# gimbal_controller.net
KiCad netlist of a schematic drawn in EAGLE
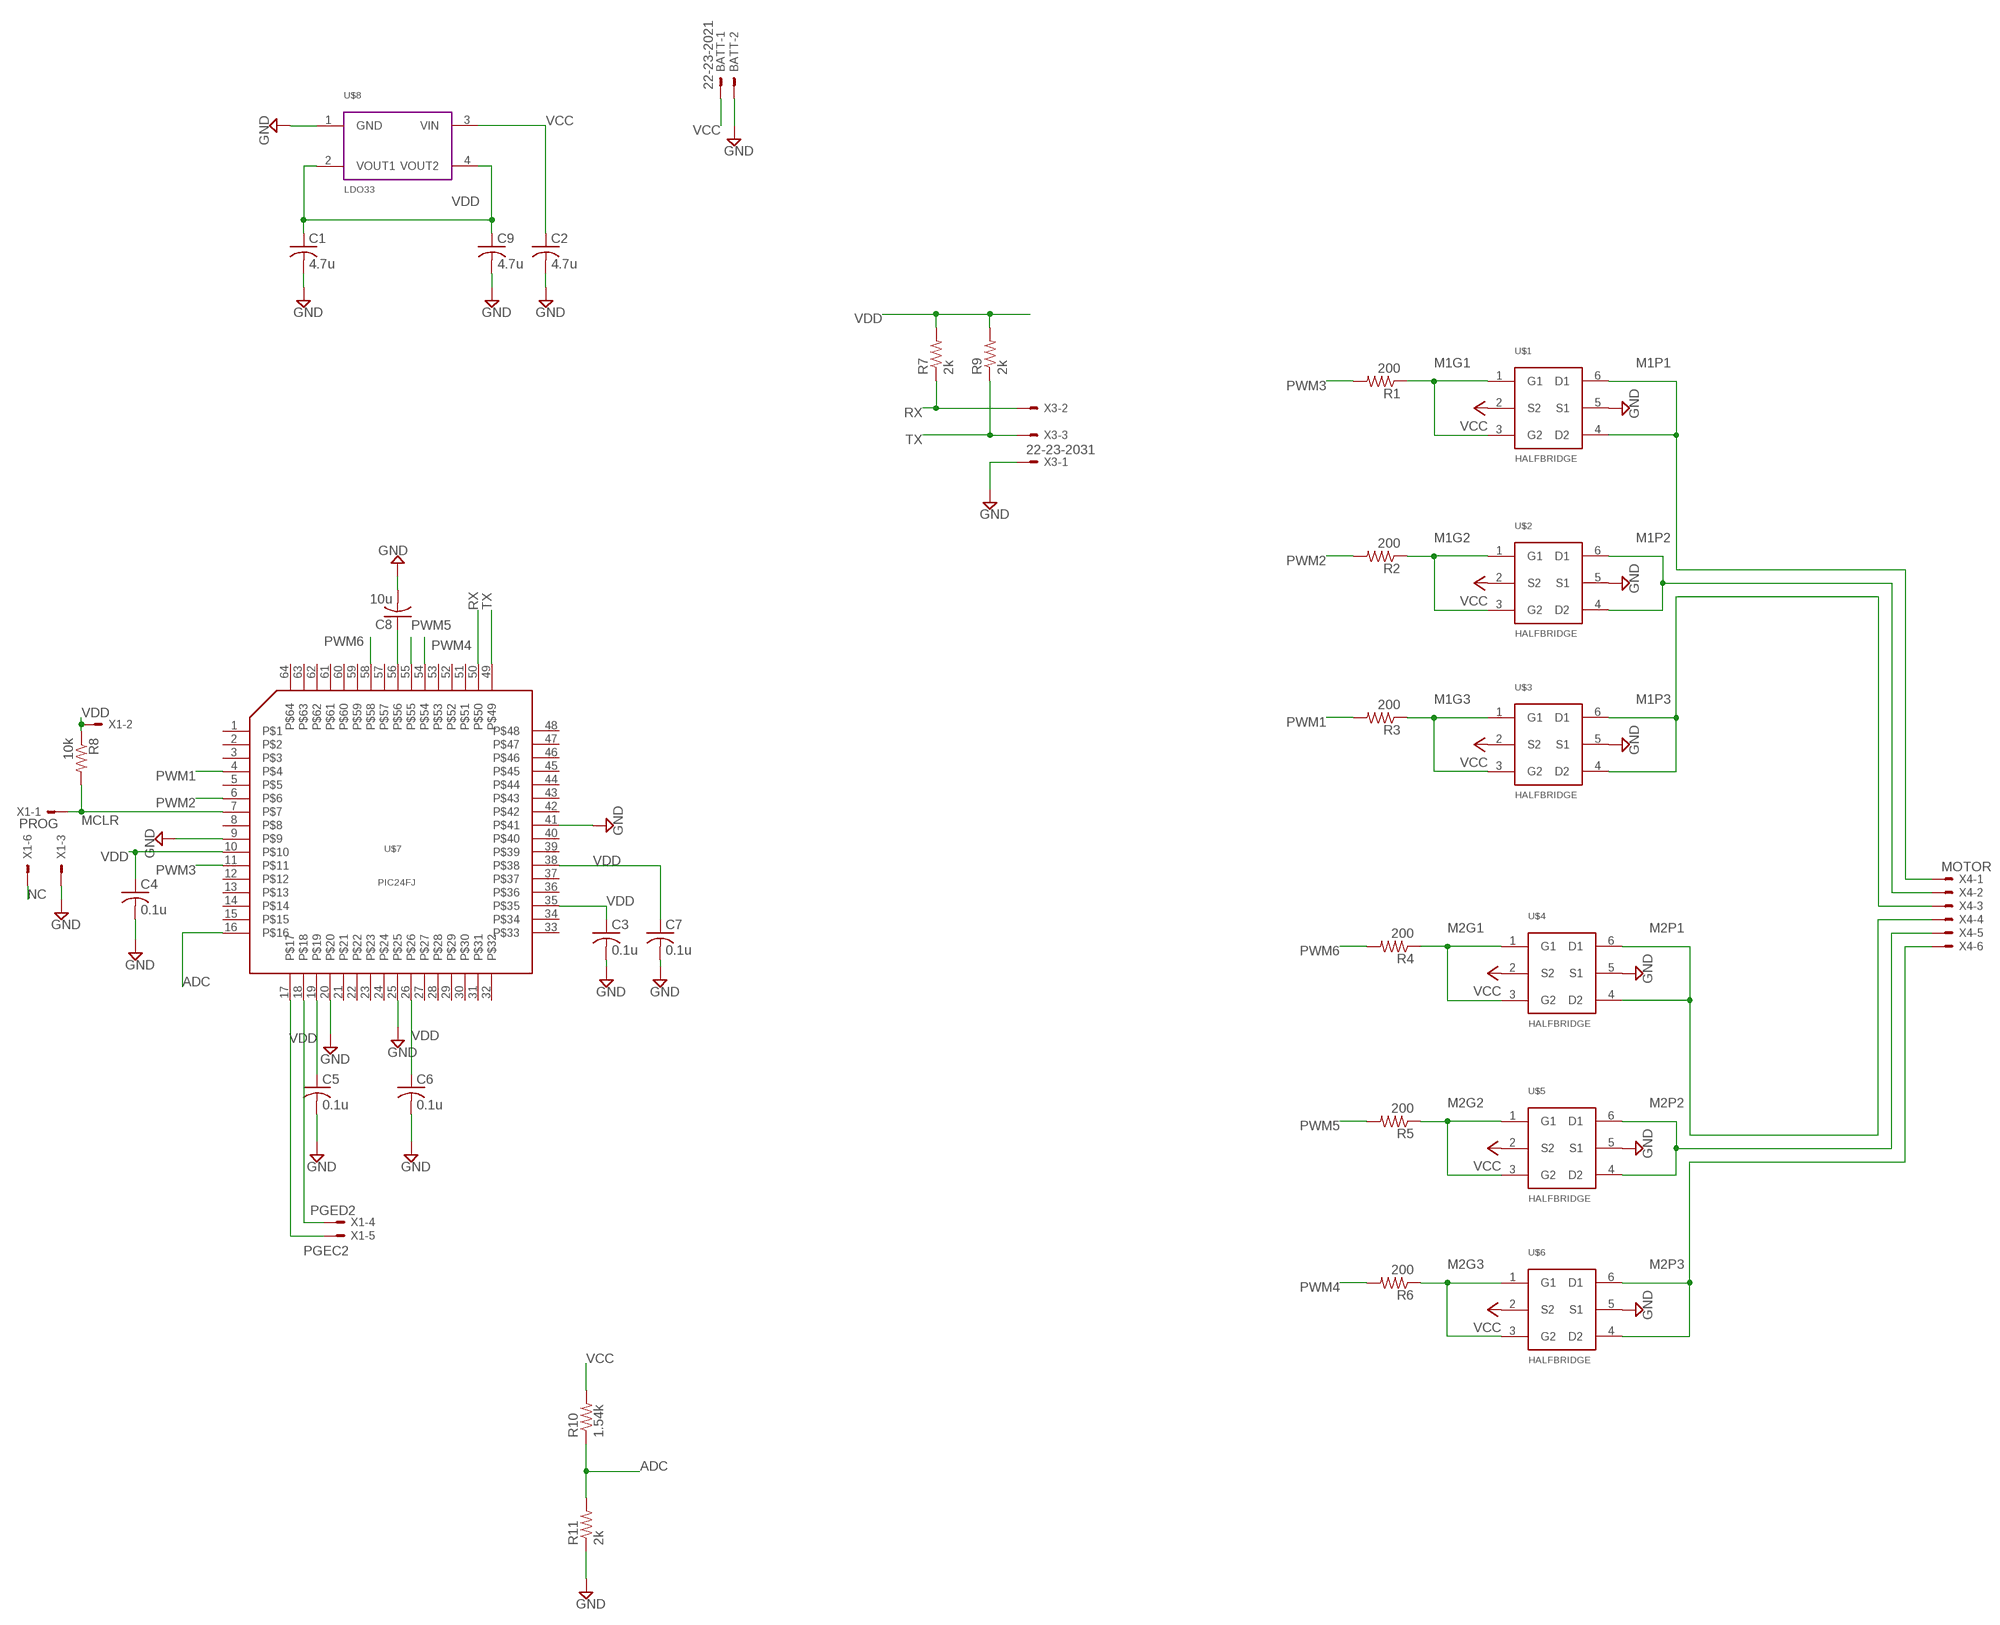
[diagram p0: schematic, sheet 1]

(export (version "E")
  (design (tool "Eeschema 10.0.6"))
  (components
    (comp (ref "BATT")
      (value "22-23-2021")
      (footprint "eagle-import:22-23-2021")
      (fields (field (name "MF") "MOLEX"))
      (libsource (lib "eagle-import") (part "22-23-2021"))
    )
    (comp (ref "C1")
      (value "4.7u")
      (footprint "eagle-import:C0805")
      (libsource (lib "eagle-import") (part "C-USC0805"))
    )
    (comp (ref "C2")
      (value "4.7u")
      (footprint "eagle-import:C0805")
      (libsource (lib "eagle-import") (part "C-USC0805"))
    )
    (comp (ref "C3")
      (value "0.1u")
      (footprint "eagle-import:C0805")
      (libsource (lib "eagle-import") (part "C-USC0805"))
    )
    (comp (ref "C4")
      (value "0.1u")
      (footprint "eagle-import:C0805")
      (libsource (lib "eagle-import") (part "C-USC0805"))
    )
    (comp (ref "C5")
      (value "0.1u")
      (footprint "eagle-import:C0805")
      (libsource (lib "eagle-import") (part "C-USC0805"))
    )
    (comp (ref "C6")
      (value "0.1u")
      (footprint "eagle-import:C0805")
      (libsource (lib "eagle-import") (part "C-USC0805"))
    )
    (comp (ref "C7")
      (value "0.1u")
      (footprint "eagle-import:C0805")
      (libsource (lib "eagle-import") (part "C-USC0805"))
    )
    (comp (ref "C8")
      (value "10u")
      (footprint "eagle-import:C0805")
      (libsource (lib "eagle-import") (part "C-USC0805"))
    )
    (comp (ref "C9")
      (value "4.7u")
      (footprint "eagle-import:C0805")
      (libsource (lib "eagle-import") (part "C-USC0805"))
    )
    (comp (ref "R1")
      (value "200")
      (footprint "eagle-import:R0805")
      (libsource (lib "eagle-import") (part "R-US_R0805"))
    )
    (comp (ref "R2")
      (value "200")
      (footprint "eagle-import:R0805")
      (libsource (lib "eagle-import") (part "R-US_R0805"))
    )
    (comp (ref "R3")
      (value "200")
      (footprint "eagle-import:R0805")
      (libsource (lib "eagle-import") (part "R-US_R0805"))
    )
    (comp (ref "R4")
      (value "200")
      (footprint "eagle-import:R0805")
      (libsource (lib "eagle-import") (part "R-US_R0805"))
    )
    (comp (ref "R5")
      (value "200")
      (footprint "eagle-import:R0805")
      (libsource (lib "eagle-import") (part "R-US_R0805"))
    )
    (comp (ref "R6")
      (value "200")
      (footprint "eagle-import:R0805")
      (libsource (lib "eagle-import") (part "R-US_R0805"))
    )
    (comp (ref "R7")
      (value "2k")
      (footprint "eagle-import:R0805")
      (libsource (lib "eagle-import") (part "resistor_R-US_R0805"))
    )
    (comp (ref "R8")
      (value "10k")
      (footprint "eagle-import:R0805")
      (libsource (lib "eagle-import") (part "R-US_R0805"))
    )
    (comp (ref "R9")
      (value "2k")
      (footprint "eagle-import:R0805")
      (libsource (lib "eagle-import") (part "resistor_R-US_R0805"))
    )
    (comp (ref "R10")
      (value "1.54k")
      (footprint "eagle-import:R0805")
      (libsource (lib "eagle-import") (part "resistor_R-US_R0805"))
    )
    (comp (ref "R11")
      (value "2k")
      (footprint "eagle-import:R0805")
      (libsource (lib "eagle-import") (part "resistor_R-US_R0805"))
    )
    (comp (ref "U$1")
      (value "HALFBRIDGE")
      (footprint "eagle-import:SSOT6")
      (libsource (lib "eagle-import") (part "HALFBRIDGE"))
    )
    (comp (ref "U$2")
      (value "HALFBRIDGE")
      (footprint "eagle-import:SSOT6")
      (libsource (lib "eagle-import") (part "HALFBRIDGE"))
    )
    (comp (ref "U$3")
      (value "HALFBRIDGE")
      (footprint "eagle-import:SSOT6")
      (libsource (lib "eagle-import") (part "HALFBRIDGE"))
    )
    (comp (ref "U$4")
      (value "HALFBRIDGE")
      (footprint "eagle-import:SSOT6")
      (libsource (lib "eagle-import") (part "HALFBRIDGE"))
    )
    (comp (ref "U$5")
      (value "HALFBRIDGE")
      (footprint "eagle-import:SSOT6")
      (libsource (lib "eagle-import") (part "HALFBRIDGE"))
    )
    (comp (ref "U$6")
      (value "HALFBRIDGE")
      (footprint "eagle-import:SSOT6")
      (libsource (lib "eagle-import") (part "HALFBRIDGE"))
    )
    (comp (ref "U$7")
      (value "PIC24FJ")
      (footprint "eagle-import:TQFP64-10X10")
      (libsource (lib "eagle-import") (part "PIC24FJ"))
    )
    (comp (ref "U$8")
      (value "LDO33")
      (footprint "eagle-import:SOT223")
      (libsource (lib "eagle-import") (part "LDO33"))
    )
    (comp (ref "X1")
      (value "PROG")
      (footprint "eagle-import:22-23-2061")
      (fields (field (name "MF") "MOLEX") (field (name "MPN") "22-23-2061"))
      (libsource (lib "eagle-import") (part "22-23-2061"))
    )
    (comp (ref "X3")
      (value "22-23-2031")
      (footprint "eagle-import:22-23-2031")
      (fields (field (name "MF") "MOLEX"))
      (libsource (lib "eagle-import") (part "22-23-2031"))
    )
    (comp (ref "X4")
      (value "MOTOR")
      (footprint "eagle-import:22-23-2061")
      (fields (field (name "MF") "MOLEX") (field (name "MPN") "22-23-2061"))
      (libsource (lib "eagle-import") (part "22-23-2061"))
    )
  )
  (nets
    (net (code "1") (name "/ADC") (class "Default")
      (node (ref "R10") (pin "1") (pinfunction "1_1") (pintype "passive"))
      (node (ref "R11") (pin "2") (pinfunction "2_2") (pintype "passive"))
      (node (ref "U$7") (pin "16") (pinfunction "P$16_16") (pintype "bidirectional"))
    )
    (net (code "2") (name "/M1G1") (class "Default")
      (node (ref "R1") (pin "1") (pinfunction "1_1") (pintype "passive"))
      (node (ref "U$1") (pin "1") (pinfunction "G1_1") (pintype "bidirectional"))
      (node (ref "U$1") (pin "3") (pinfunction "G2_3") (pintype "bidirectional"))
    )
    (net (code "3") (name "/M1G2") (class "Default")
      (node (ref "R2") (pin "1") (pinfunction "1_1") (pintype "passive"))
      (node (ref "U$2") (pin "1") (pinfunction "G1_1") (pintype "bidirectional"))
      (node (ref "U$2") (pin "3") (pinfunction "G2_3") (pintype "bidirectional"))
    )
    (net (code "4") (name "/M1G3") (class "Default")
      (node (ref "R3") (pin "1") (pinfunction "1_1") (pintype "passive"))
      (node (ref "U$3") (pin "1") (pinfunction "G1_1") (pintype "bidirectional"))
      (node (ref "U$3") (pin "3") (pinfunction "G2_3") (pintype "bidirectional"))
    )
    (net (code "5") (name "/M1P1") (class "Default")
      (node (ref "U$1") (pin "4") (pinfunction "D2_4") (pintype "bidirectional"))
      (node (ref "U$1") (pin "6") (pinfunction "D1_6") (pintype "bidirectional"))
      (node (ref "X4") (pin "1") (pinfunction "S_1") (pintype "passive"))
    )
    (net (code "6") (name "/M1P2") (class "Default")
      (node (ref "U$2") (pin "4") (pinfunction "D2_4") (pintype "bidirectional"))
      (node (ref "U$2") (pin "6") (pinfunction "D1_6") (pintype "bidirectional"))
      (node (ref "X4") (pin "2") (pinfunction "S_2") (pintype "passive"))
    )
    (net (code "7") (name "/M1P3") (class "Default")
      (node (ref "U$3") (pin "4") (pinfunction "D2_4") (pintype "bidirectional"))
      (node (ref "U$3") (pin "6") (pinfunction "D1_6") (pintype "bidirectional"))
      (node (ref "X4") (pin "3") (pinfunction "S_3") (pintype "passive"))
    )
    (net (code "8") (name "/M2G1") (class "Default")
      (node (ref "R4") (pin "1") (pinfunction "1_1") (pintype "passive"))
      (node (ref "U$4") (pin "1") (pinfunction "G1_1") (pintype "bidirectional"))
      (node (ref "U$4") (pin "3") (pinfunction "G2_3") (pintype "bidirectional"))
    )
    (net (code "9") (name "/M2G2") (class "Default")
      (node (ref "R5") (pin "1") (pinfunction "1_1") (pintype "passive"))
      (node (ref "U$5") (pin "1") (pinfunction "G1_1") (pintype "bidirectional"))
      (node (ref "U$5") (pin "3") (pinfunction "G2_3") (pintype "bidirectional"))
    )
    (net (code "10") (name "/M2G3") (class "Default")
      (node (ref "R6") (pin "1") (pinfunction "1_1") (pintype "passive"))
      (node (ref "U$6") (pin "1") (pinfunction "G1_1") (pintype "bidirectional"))
      (node (ref "U$6") (pin "3") (pinfunction "G2_3") (pintype "bidirectional"))
    )
    (net (code "11") (name "/M2P1") (class "Default")
      (node (ref "U$4") (pin "4") (pinfunction "D2_4") (pintype "bidirectional"))
      (node (ref "U$4") (pin "6") (pinfunction "D1_6") (pintype "bidirectional"))
      (node (ref "X4") (pin "4") (pinfunction "S_4") (pintype "passive"))
    )
    (net (code "12") (name "/M2P2") (class "Default")
      (node (ref "U$5") (pin "4") (pinfunction "D2_4") (pintype "bidirectional"))
      (node (ref "U$5") (pin "6") (pinfunction "D1_6") (pintype "bidirectional"))
      (node (ref "X4") (pin "5") (pinfunction "S_5") (pintype "passive"))
    )
    (net (code "13") (name "/M2P3") (class "Default")
      (node (ref "U$6") (pin "4") (pinfunction "D2_4") (pintype "bidirectional"))
      (node (ref "U$6") (pin "6") (pinfunction "D1_6") (pintype "bidirectional"))
      (node (ref "X4") (pin "6") (pinfunction "S_6") (pintype "passive"))
    )
    (net (code "14") (name "/MCLR") (class "Default")
      (node (ref "R8") (pin "2") (pinfunction "2_2") (pintype "passive"))
      (node (ref "U$7") (pin "7") (pinfunction "P$7_7") (pintype "bidirectional"))
      (node (ref "X1") (pin "1") (pinfunction "S_1") (pintype "passive"))
    )
    (net (code "15") (name "/NC") (class "Default")
      (node (ref "X1") (pin "6") (pinfunction "S_6") (pintype "passive"))
    )
    (net (code "16") (name "/PGEC2") (class "Default")
      (node (ref "U$7") (pin "17") (pinfunction "P$17_17") (pintype "bidirectional"))
      (node (ref "X1") (pin "5") (pinfunction "S_5") (pintype "passive"))
    )
    (net (code "17") (name "/PGED2") (class "Default")
      (node (ref "U$7") (pin "18") (pinfunction "P$18_18") (pintype "bidirectional"))
      (node (ref "X1") (pin "4") (pinfunction "S_4") (pintype "passive"))
    )
    (net (code "18") (name "/PWM1") (class "Default")
      (node (ref "R3") (pin "2") (pinfunction "2_2") (pintype "passive"))
      (node (ref "U$7") (pin "4") (pinfunction "P$4_4") (pintype "bidirectional"))
    )
    (net (code "19") (name "/PWM2") (class "Default")
      (node (ref "R2") (pin "2") (pinfunction "2_2") (pintype "passive"))
      (node (ref "U$7") (pin "6") (pinfunction "P$6_6") (pintype "bidirectional"))
    )
    (net (code "20") (name "/PWM3") (class "Default")
      (node (ref "R1") (pin "2") (pinfunction "2_2") (pintype "passive"))
      (node (ref "U$7") (pin "11") (pinfunction "P$11_11") (pintype "bidirectional"))
    )
    (net (code "21") (name "/PWM4") (class "Default")
      (node (ref "R6") (pin "2") (pinfunction "2_2") (pintype "passive"))
      (node (ref "U$7") (pin "54") (pinfunction "P$54_54") (pintype "bidirectional"))
    )
    (net (code "22") (name "/PWM5") (class "Default")
      (node (ref "R5") (pin "2") (pinfunction "2_2") (pintype "passive"))
      (node (ref "U$7") (pin "55") (pinfunction "P$55_55") (pintype "bidirectional"))
    )
    (net (code "23") (name "/PWM6") (class "Default")
      (node (ref "R4") (pin "2") (pinfunction "2_2") (pintype "passive"))
      (node (ref "U$7") (pin "58") (pinfunction "P$58_58") (pintype "bidirectional"))
    )
    (net (code "24") (name "/RX") (class "Default")
      (node (ref "R7") (pin "1") (pinfunction "1_1") (pintype "passive"))
      (node (ref "U$7") (pin "50") (pinfunction "P$50_50") (pintype "bidirectional"))
      (node (ref "X3") (pin "2") (pinfunction "S_2") (pintype "passive"))
    )
    (net (code "25") (name "/TX") (class "Default")
      (node (ref "R9") (pin "1") (pinfunction "1_1") (pintype "passive"))
      (node (ref "U$7") (pin "49") (pinfunction "P$49_49") (pintype "bidirectional"))
      (node (ref "X3") (pin "3") (pinfunction "S_3") (pintype "passive"))
    )
    (net (code "26") (name "/VDD") (class "Default")
      (node (ref "C1") (pin "1") (pinfunction "1_1") (pintype "passive"))
      (node (ref "C3") (pin "1") (pinfunction "1_1") (pintype "passive"))
      (node (ref "C4") (pin "1") (pinfunction "1_1") (pintype "passive"))
      (node (ref "C5") (pin "1") (pinfunction "1_1") (pintype "passive"))
      (node (ref "C6") (pin "1") (pinfunction "1_1") (pintype "passive"))
      (node (ref "C7") (pin "1") (pinfunction "1_1") (pintype "passive"))
      (node (ref "C9") (pin "1") (pinfunction "1_1") (pintype "passive"))
      (node (ref "R7") (pin "2") (pinfunction "2_2") (pintype "passive"))
      (node (ref "R8") (pin "1") (pinfunction "1_1") (pintype "passive"))
      (node (ref "R9") (pin "2") (pinfunction "2_2") (pintype "passive"))
      (node (ref "U$7") (pin "10") (pinfunction "P$10_10") (pintype "bidirectional"))
      (node (ref "U$7") (pin "19") (pinfunction "P$19_19") (pintype "bidirectional"))
      (node (ref "U$7") (pin "26") (pinfunction "P$26_26") (pintype "bidirectional"))
      (node (ref "U$7") (pin "35") (pinfunction "P$35_35") (pintype "bidirectional"))
      (node (ref "U$7") (pin "38") (pinfunction "P$38_38") (pintype "bidirectional"))
      (node (ref "U$8") (pin "2") (pinfunction "VOUT1_2") (pintype "bidirectional"))
      (node (ref "U$8") (pin "4") (pinfunction "VOUT2_4") (pintype "bidirectional"))
      (node (ref "X1") (pin "2") (pinfunction "S_2") (pintype "passive"))
    )
    (net (code "27") (name "GND") (class "Default")
      (node (ref "BATT") (pin "2") (pinfunction "S_2") (pintype "passive"))
      (node (ref "C1") (pin "2") (pinfunction "2_2") (pintype "passive"))
      (node (ref "C2") (pin "2") (pinfunction "2_2") (pintype "passive"))
      (node (ref "C3") (pin "2") (pinfunction "2_2") (pintype "passive"))
      (node (ref "C4") (pin "2") (pinfunction "2_2") (pintype "passive"))
      (node (ref "C5") (pin "2") (pinfunction "2_2") (pintype "passive"))
      (node (ref "C6") (pin "2") (pinfunction "2_2") (pintype "passive"))
      (node (ref "C7") (pin "2") (pinfunction "2_2") (pintype "passive"))
      (node (ref "C8") (pin "2") (pinfunction "2_2") (pintype "passive"))
      (node (ref "C9") (pin "2") (pinfunction "2_2") (pintype "passive"))
      (node (ref "R11") (pin "1") (pinfunction "1_1") (pintype "passive"))
      (node (ref "U$1") (pin "5") (pinfunction "S1_5") (pintype "bidirectional"))
      (node (ref "U$2") (pin "5") (pinfunction "S1_5") (pintype "bidirectional"))
      (node (ref "U$3") (pin "5") (pinfunction "S1_5") (pintype "bidirectional"))
      (node (ref "U$4") (pin "5") (pinfunction "S1_5") (pintype "bidirectional"))
      (node (ref "U$5") (pin "5") (pinfunction "S1_5") (pintype "bidirectional"))
      (node (ref "U$6") (pin "5") (pinfunction "S1_5") (pintype "bidirectional"))
      (node (ref "U$7") (pin "20") (pinfunction "P$20_20") (pintype "bidirectional"))
      (node (ref "U$7") (pin "25") (pinfunction "P$25_25") (pintype "bidirectional"))
      (node (ref "U$7") (pin "41") (pinfunction "P$41_41") (pintype "bidirectional"))
      (node (ref "U$7") (pin "9") (pinfunction "P$9_9") (pintype "bidirectional"))
      (node (ref "U$8") (pin "1") (pinfunction "GND_1") (pintype "bidirectional"))
      (node (ref "X1") (pin "3") (pinfunction "S_3") (pintype "passive"))
      (node (ref "X3") (pin "1") (pinfunction "S_1") (pintype "passive"))
    )
    (net (code "28") (name "Net-(U$7-P$56)") (class "Default")
      (node (ref "C8") (pin "1") (pinfunction "1_1") (pintype "passive"))
      (node (ref "U$7") (pin "56") (pinfunction "P$56_56") (pintype "bidirectional"))
    )
    (net (code "29") (name "VCC") (class "Default")
      (node (ref "BATT") (pin "1") (pinfunction "S_1") (pintype "passive"))
      (node (ref "C2") (pin "1") (pinfunction "1_1") (pintype "passive"))
      (node (ref "R10") (pin "2") (pinfunction "2_2") (pintype "passive"))
      (node (ref "U$1") (pin "2") (pinfunction "S2_2") (pintype "bidirectional"))
      (node (ref "U$2") (pin "2") (pinfunction "S2_2") (pintype "bidirectional"))
      (node (ref "U$3") (pin "2") (pinfunction "S2_2") (pintype "bidirectional"))
      (node (ref "U$4") (pin "2") (pinfunction "S2_2") (pintype "bidirectional"))
      (node (ref "U$5") (pin "2") (pinfunction "S2_2") (pintype "bidirectional"))
      (node (ref "U$6") (pin "2") (pinfunction "S2_2") (pintype "bidirectional"))
      (node (ref "U$8") (pin "3") (pinfunction "VIN_3") (pintype "bidirectional"))
    )
    (net (code "30") (name "unconnected-(U$7-P$1-Pad1)") (class "Default")
      (node (ref "U$7") (pin "1") (pinfunction "P$1_1") (pintype "bidirectional"))
    )
    (net (code "31") (name "unconnected-(U$7-P$2-Pad2)") (class "Default")
      (node (ref "U$7") (pin "2") (pinfunction "P$2_2") (pintype "bidirectional"))
    )
    (net (code "32") (name "unconnected-(U$7-P$3-Pad3)") (class "Default")
      (node (ref "U$7") (pin "3") (pinfunction "P$3_3") (pintype "bidirectional"))
    )
    (net (code "33") (name "unconnected-(U$7-P$5-Pad5)") (class "Default")
      (node (ref "U$7") (pin "5") (pinfunction "P$5_5") (pintype "bidirectional"))
    )
    (net (code "34") (name "unconnected-(U$7-P$8-Pad8)") (class "Default")
      (node (ref "U$7") (pin "8") (pinfunction "P$8_8") (pintype "bidirectional"))
    )
    (net (code "35") (name "unconnected-(U$7-P$12-Pad12)") (class "Default")
      (node (ref "U$7") (pin "12") (pinfunction "P$12_12") (pintype "bidirectional"))
    )
    (net (code "36") (name "unconnected-(U$7-P$13-Pad13)") (class "Default")
      (node (ref "U$7") (pin "13") (pinfunction "P$13_13") (pintype "bidirectional"))
    )
    (net (code "37") (name "unconnected-(U$7-P$14-Pad14)") (class "Default")
      (node (ref "U$7") (pin "14") (pinfunction "P$14_14") (pintype "bidirectional"))
    )
    (net (code "38") (name "unconnected-(U$7-P$15-Pad15)") (class "Default")
      (node (ref "U$7") (pin "15") (pinfunction "P$15_15") (pintype "bidirectional"))
    )
    (net (code "39") (name "unconnected-(U$7-P$21-Pad21)") (class "Default")
      (node (ref "U$7") (pin "21") (pinfunction "P$21_21") (pintype "bidirectional"))
    )
    (net (code "40") (name "unconnected-(U$7-P$22-Pad22)") (class "Default")
      (node (ref "U$7") (pin "22") (pinfunction "P$22_22") (pintype "bidirectional"))
    )
    (net (code "41") (name "unconnected-(U$7-P$23-Pad23)") (class "Default")
      (node (ref "U$7") (pin "23") (pinfunction "P$23_23") (pintype "bidirectional"))
    )
    (net (code "42") (name "unconnected-(U$7-P$24-Pad24)") (class "Default")
      (node (ref "U$7") (pin "24") (pinfunction "P$24_24") (pintype "bidirectional"))
    )
    (net (code "43") (name "unconnected-(U$7-P$27-Pad27)") (class "Default")
      (node (ref "U$7") (pin "27") (pinfunction "P$27_27") (pintype "bidirectional"))
    )
    (net (code "44") (name "unconnected-(U$7-P$28-Pad28)") (class "Default")
      (node (ref "U$7") (pin "28") (pinfunction "P$28_28") (pintype "bidirectional"))
    )
    (net (code "45") (name "unconnected-(U$7-P$29-Pad29)") (class "Default")
      (node (ref "U$7") (pin "29") (pinfunction "P$29_29") (pintype "bidirectional"))
    )
    (net (code "46") (name "unconnected-(U$7-P$30-Pad30)") (class "Default")
      (node (ref "U$7") (pin "30") (pinfunction "P$30_30") (pintype "bidirectional"))
    )
    (net (code "47") (name "unconnected-(U$7-P$31-Pad31)") (class "Default")
      (node (ref "U$7") (pin "31") (pinfunction "P$31_31") (pintype "bidirectional"))
    )
    (net (code "48") (name "unconnected-(U$7-P$32-Pad32)") (class "Default")
      (node (ref "U$7") (pin "32") (pinfunction "P$32_32") (pintype "bidirectional"))
    )
    (net (code "49") (name "unconnected-(U$7-P$33-Pad33)") (class "Default")
      (node (ref "U$7") (pin "33") (pinfunction "P$33_33") (pintype "bidirectional"))
    )
    (net (code "50") (name "unconnected-(U$7-P$34-Pad34)") (class "Default")
      (node (ref "U$7") (pin "34") (pinfunction "P$34_34") (pintype "bidirectional"))
    )
    (net (code "51") (name "unconnected-(U$7-P$36-Pad36)") (class "Default")
      (node (ref "U$7") (pin "36") (pinfunction "P$36_36") (pintype "bidirectional"))
    )
    (net (code "52") (name "unconnected-(U$7-P$37-Pad37)") (class "Default")
      (node (ref "U$7") (pin "37") (pinfunction "P$37_37") (pintype "bidirectional"))
    )
    (net (code "53") (name "unconnected-(U$7-P$39-Pad39)") (class "Default")
      (node (ref "U$7") (pin "39") (pinfunction "P$39_39") (pintype "bidirectional"))
    )
    (net (code "54") (name "unconnected-(U$7-P$40-Pad40)") (class "Default")
      (node (ref "U$7") (pin "40") (pinfunction "P$40_40") (pintype "bidirectional"))
    )
    (net (code "55") (name "unconnected-(U$7-P$42-Pad42)") (class "Default")
      (node (ref "U$7") (pin "42") (pinfunction "P$42_42") (pintype "bidirectional"))
    )
    (net (code "56") (name "unconnected-(U$7-P$43-Pad43)") (class "Default")
      (node (ref "U$7") (pin "43") (pinfunction "P$43_43") (pintype "bidirectional"))
    )
    (net (code "57") (name "unconnected-(U$7-P$44-Pad44)") (class "Default")
      (node (ref "U$7") (pin "44") (pinfunction "P$44_44") (pintype "bidirectional"))
    )
    (net (code "58") (name "unconnected-(U$7-P$45-Pad45)") (class "Default")
      (node (ref "U$7") (pin "45") (pinfunction "P$45_45") (pintype "bidirectional"))
    )
    (net (code "59") (name "unconnected-(U$7-P$46-Pad46)") (class "Default")
      (node (ref "U$7") (pin "46") (pinfunction "P$46_46") (pintype "bidirectional"))
    )
    (net (code "60") (name "unconnected-(U$7-P$47-Pad47)") (class "Default")
      (node (ref "U$7") (pin "47") (pinfunction "P$47_47") (pintype "bidirectional"))
    )
    (net (code "61") (name "unconnected-(U$7-P$48-Pad48)") (class "Default")
      (node (ref "U$7") (pin "48") (pinfunction "P$48_48") (pintype "bidirectional"))
    )
    (net (code "62") (name "unconnected-(U$7-P$51-Pad51)") (class "Default")
      (node (ref "U$7") (pin "51") (pinfunction "P$51_51") (pintype "bidirectional"))
    )
    (net (code "63") (name "unconnected-(U$7-P$52-Pad52)") (class "Default")
      (node (ref "U$7") (pin "52") (pinfunction "P$52_52") (pintype "bidirectional"))
    )
    (net (code "64") (name "unconnected-(U$7-P$53-Pad53)") (class "Default")
      (node (ref "U$7") (pin "53") (pinfunction "P$53_53") (pintype "bidirectional"))
    )
    (net (code "65") (name "unconnected-(U$7-P$57-Pad57)") (class "Default")
      (node (ref "U$7") (pin "57") (pinfunction "P$57_57") (pintype "bidirectional"))
    )
    (net (code "66") (name "unconnected-(U$7-P$59-Pad59)") (class "Default")
      (node (ref "U$7") (pin "59") (pinfunction "P$59_59") (pintype "bidirectional"))
    )
    (net (code "67") (name "unconnected-(U$7-P$60-Pad60)") (class "Default")
      (node (ref "U$7") (pin "60") (pinfunction "P$60_60") (pintype "bidirectional"))
    )
    (net (code "68") (name "unconnected-(U$7-P$61-Pad61)") (class "Default")
      (node (ref "U$7") (pin "61") (pinfunction "P$61_61") (pintype "bidirectional"))
    )
    (net (code "69") (name "unconnected-(U$7-P$62-Pad62)") (class "Default")
      (node (ref "U$7") (pin "62") (pinfunction "P$62_62") (pintype "bidirectional"))
    )
    (net (code "70") (name "unconnected-(U$7-P$63-Pad63)") (class "Default")
      (node (ref "U$7") (pin "63") (pinfunction "P$63_63") (pintype "bidirectional"))
    )
    (net (code "71") (name "unconnected-(U$7-P$64-Pad64)") (class "Default")
      (node (ref "U$7") (pin "64") (pinfunction "P$64_64") (pintype "bidirectional"))
    )
  )
)
